# URC-PASSTHROUGH-USB2.net
KiCad netlist of a schematic drawn in EAGLE
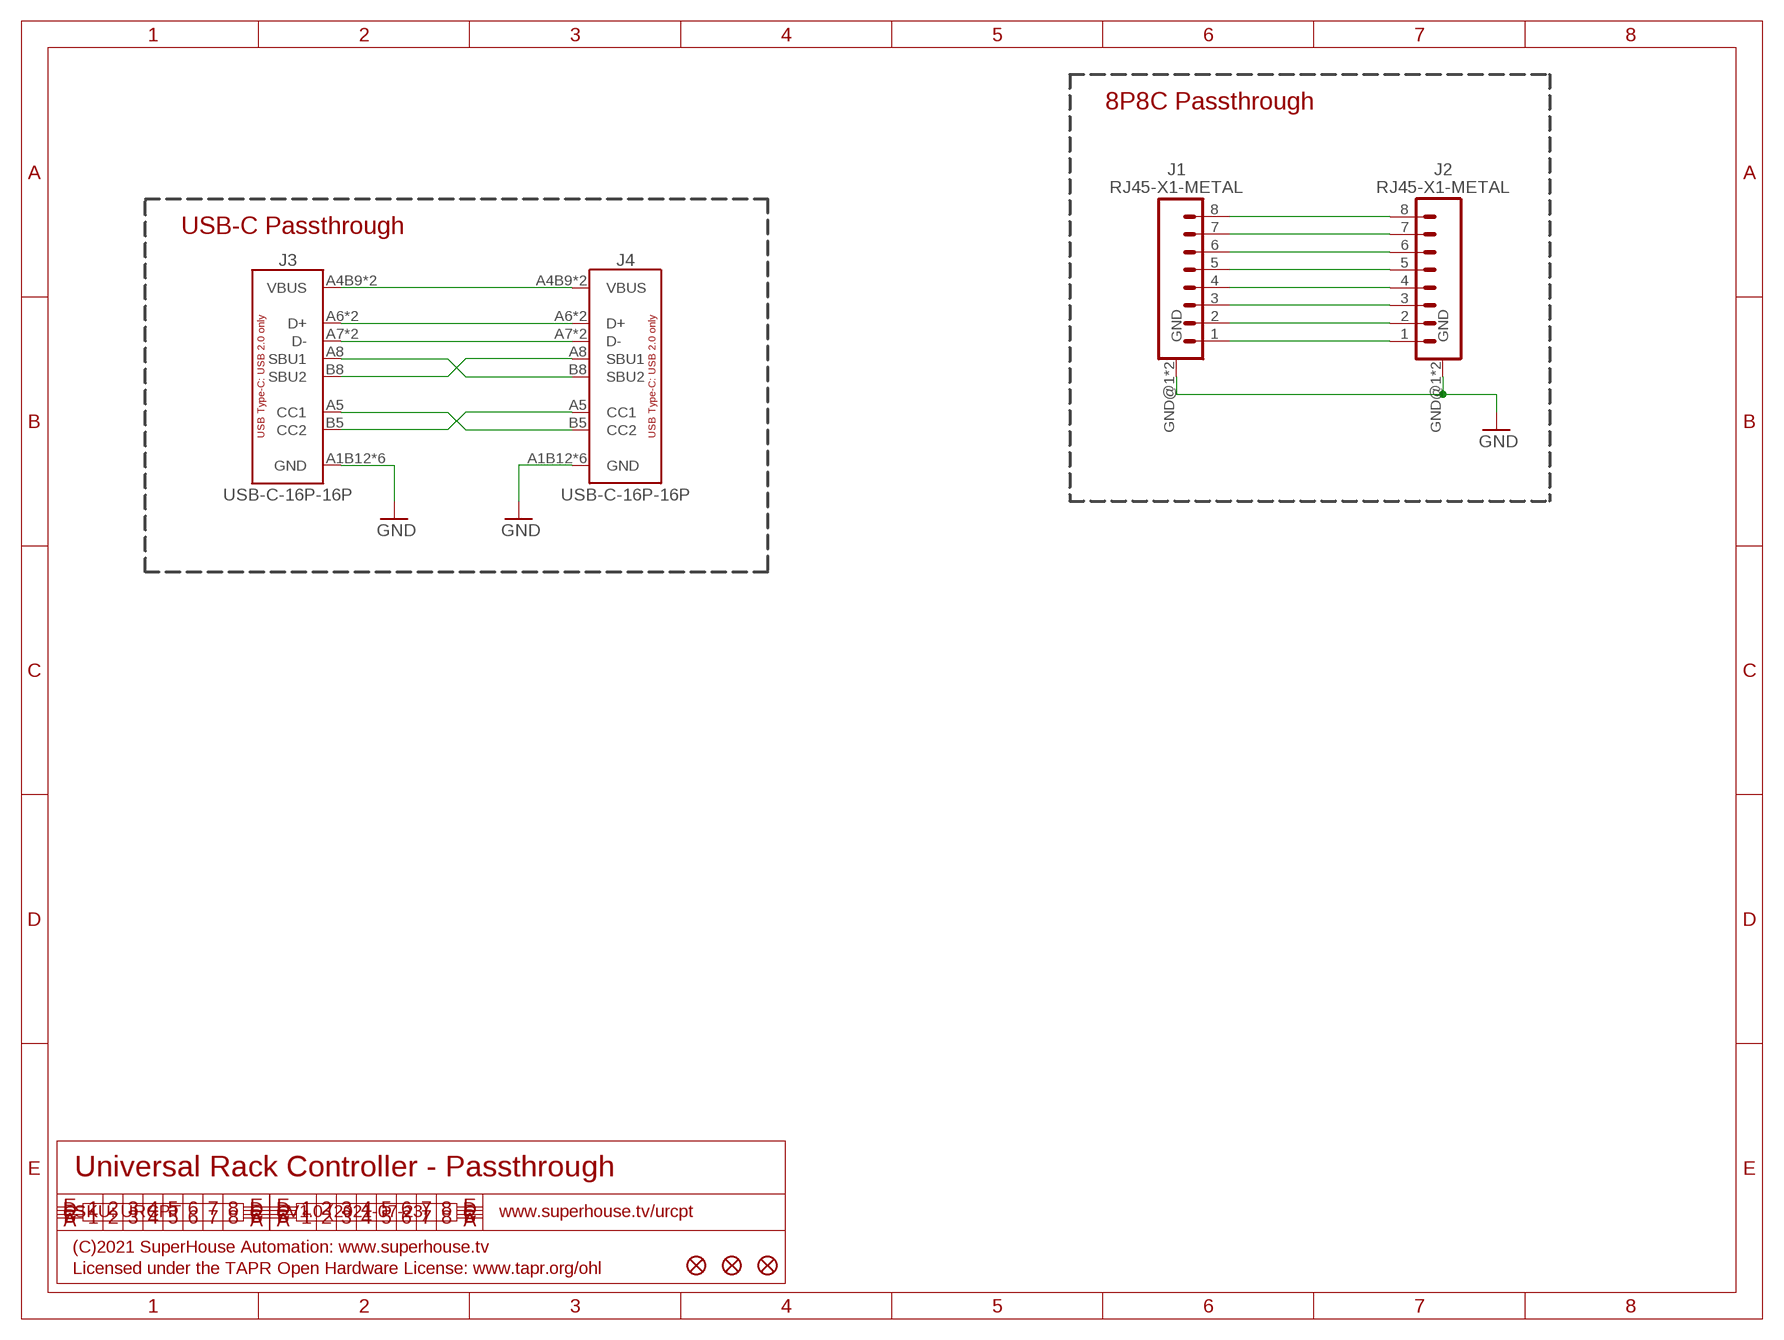
[diagram p0: schematic, sheet 1]

(export (version "E")
  (design (tool "Eeschema 10.0.6"))
  (components
    (comp (ref "FID1")
      (value "FIDUCIAL1X2.5")
      (footprint "eagle-import:FIDUCIAL-1X2.5")
      (libsource (lib "eagle-import") (part "FIDUCIAL1X2.5"))
    )
    (comp (ref "FID2")
      (value "FIDUCIAL1X2.5")
      (footprint "eagle-import:FIDUCIAL-1X2.5")
      (libsource (lib "eagle-import") (part "FIDUCIAL1X2.5"))
    )
    (comp (ref "FID3")
      (value "FIDUCIAL1X2.5")
      (footprint "eagle-import:FIDUCIAL-1X2.5")
      (libsource (lib "eagle-import") (part "FIDUCIAL1X2.5"))
    )
    (comp (ref "J1")
      (value "RJ45-X1-METAL")
      (footprint "eagle-import:RJ45-1X1")
      (libsource (lib "eagle-import") (part "RJ45-X1-METAL"))
    )
    (comp (ref "J2")
      (value "RJ45-X1-METAL")
      (footprint "eagle-import:RJ45-1X1")
      (libsource (lib "eagle-import") (part "RJ45-X1-METAL"))
    )
    (comp (ref "J3")
      (value "USB-C-16P-16P")
      (footprint "eagle-import:USB-C-16P")
      (libsource (lib "eagle-import") (part "USB-C-16P-16P"))
    )
    (comp (ref "J4")
      (value "USB-C-16P-16P")
      (footprint "eagle-import:USB-C-16P")
      (libsource (lib "eagle-import") (part "USB-C-16P-16P"))
    )
  )
  (nets
    (net (code "1") (name "GND") (class "Default")
      (node (ref "J1") (pin "GND@1") (pinfunction "GND_GND@1") (pintype "bidirectional"))
      (node (ref "J1") (pin "GND@2") (pinfunction "GND_GND@2") (pintype "bidirectional"))
      (node (ref "J2") (pin "GND@1") (pinfunction "GND_GND@1") (pintype "bidirectional"))
      (node (ref "J2") (pin "GND@2") (pinfunction "GND_GND@2") (pintype "bidirectional"))
      (node (ref "J3") (pin "A12B1") (pinfunction "GND_A12B1") (pintype "power_in"))
      (node (ref "J3") (pin "A1B12") (pinfunction "GND_A1B12") (pintype "power_in"))
      (node (ref "J3") (pin "FIX1") (pinfunction "GND_FIX1") (pintype "power_in"))
      (node (ref "J3") (pin "FIX2") (pinfunction "GND_FIX2") (pintype "power_in"))
      (node (ref "J3") (pin "FIX3") (pinfunction "GND_FIX3") (pintype "power_in"))
      (node (ref "J3") (pin "FIX4") (pinfunction "GND_FIX4") (pintype "power_in"))
      (node (ref "J4") (pin "A12B1") (pinfunction "GND_A12B1") (pintype "power_in"))
      (node (ref "J4") (pin "A1B12") (pinfunction "GND_A1B12") (pintype "power_in"))
      (node (ref "J4") (pin "FIX1") (pinfunction "GND_FIX1") (pintype "power_in"))
      (node (ref "J4") (pin "FIX2") (pinfunction "GND_FIX2") (pintype "power_in"))
      (node (ref "J4") (pin "FIX3") (pinfunction "GND_FIX3") (pintype "power_in"))
      (node (ref "J4") (pin "FIX4") (pinfunction "GND_FIX4") (pintype "power_in"))
    )
    (net (code "2") (name "Net-(J1-Pad1)") (class "Default")
      (node (ref "J1") (pin "1") (pinfunction "1_1") (pintype "passive"))
      (node (ref "J2") (pin "1") (pinfunction "1_1") (pintype "passive"))
    )
    (net (code "3") (name "Net-(J1-Pad2)") (class "Default")
      (node (ref "J1") (pin "2") (pinfunction "2_2") (pintype "passive"))
      (node (ref "J2") (pin "2") (pinfunction "2_2") (pintype "passive"))
    )
    (net (code "4") (name "Net-(J1-Pad3)") (class "Default")
      (node (ref "J1") (pin "3") (pinfunction "3_3") (pintype "passive"))
      (node (ref "J2") (pin "3") (pinfunction "3_3") (pintype "passive"))
    )
    (net (code "5") (name "Net-(J1-Pad4)") (class "Default")
      (node (ref "J1") (pin "4") (pinfunction "4_4") (pintype "passive"))
      (node (ref "J2") (pin "4") (pinfunction "4_4") (pintype "passive"))
    )
    (net (code "6") (name "Net-(J1-Pad5)") (class "Default")
      (node (ref "J1") (pin "5") (pinfunction "5_5") (pintype "passive"))
      (node (ref "J2") (pin "5") (pinfunction "5_5") (pintype "passive"))
    )
    (net (code "7") (name "Net-(J1-Pad6)") (class "Default")
      (node (ref "J1") (pin "6") (pinfunction "6_6") (pintype "passive"))
      (node (ref "J2") (pin "6") (pinfunction "6_6") (pintype "passive"))
    )
    (net (code "8") (name "Net-(J1-Pad7)") (class "Default")
      (node (ref "J1") (pin "7") (pinfunction "7_7") (pintype "passive"))
      (node (ref "J2") (pin "7") (pinfunction "7_7") (pintype "passive"))
    )
    (net (code "9") (name "Net-(J1-Pad8)") (class "Default")
      (node (ref "J1") (pin "8") (pinfunction "8_8") (pintype "passive"))
      (node (ref "J2") (pin "8") (pinfunction "8_8") (pintype "passive"))
    )
    (net (code "10") (name "Net-(J3-CC1)") (class "Default")
      (node (ref "J3") (pin "A5") (pinfunction "CC1_A5") (pintype "bidirectional"))
      (node (ref "J4") (pin "B5") (pinfunction "CC2_B5") (pintype "bidirectional"))
    )
    (net (code "11") (name "Net-(J3-CC2)") (class "Default")
      (node (ref "J3") (pin "B5") (pinfunction "CC2_B5") (pintype "bidirectional"))
      (node (ref "J4") (pin "A5") (pinfunction "CC1_A5") (pintype "bidirectional"))
    )
    (net (code "12") (name "Net-(J3-D+-PadA6)") (class "Default")
      (node (ref "J3") (pin "A6") (pinfunction "D+_A6") (pintype "bidirectional"))
      (node (ref "J3") (pin "B6") (pinfunction "D+_B6") (pintype "bidirectional"))
      (node (ref "J4") (pin "A6") (pinfunction "D+_A6") (pintype "bidirectional"))
      (node (ref "J4") (pin "B6") (pinfunction "D+_B6") (pintype "bidirectional"))
    )
    (net (code "13") (name "Net-(J3-D--PadA7)") (class "Default")
      (node (ref "J3") (pin "A7") (pinfunction "D-_A7") (pintype "bidirectional"))
      (node (ref "J3") (pin "B7") (pinfunction "D-_B7") (pintype "bidirectional"))
      (node (ref "J4") (pin "A7") (pinfunction "D-_A7") (pintype "bidirectional"))
      (node (ref "J4") (pin "B7") (pinfunction "D-_B7") (pintype "bidirectional"))
    )
    (net (code "14") (name "Net-(J3-SBU1)") (class "Default")
      (node (ref "J3") (pin "A8") (pinfunction "SBU1_A8") (pintype "bidirectional"))
      (node (ref "J4") (pin "B8") (pinfunction "SBU2_B8") (pintype "bidirectional"))
    )
    (net (code "15") (name "Net-(J3-SBU2)") (class "Default")
      (node (ref "J3") (pin "B8") (pinfunction "SBU2_B8") (pintype "bidirectional"))
      (node (ref "J4") (pin "A8") (pinfunction "SBU1_A8") (pintype "bidirectional"))
    )
    (net (code "16") (name "Net-(J3-VBUS-PadA4B9)") (class "Default")
      (node (ref "J3") (pin "A4B9") (pinfunction "VBUS_A4B9") (pintype "power_in"))
      (node (ref "J3") (pin "A9B4") (pinfunction "VBUS_A9B4") (pintype "power_in"))
      (node (ref "J4") (pin "A4B9") (pinfunction "VBUS_A4B9") (pintype "power_in"))
      (node (ref "J4") (pin "A9B4") (pinfunction "VBUS_A9B4") (pintype "power_in"))
    )
  )
)
